# TOP.net
KiCad netlist of a schematic drawn in Altium Designer
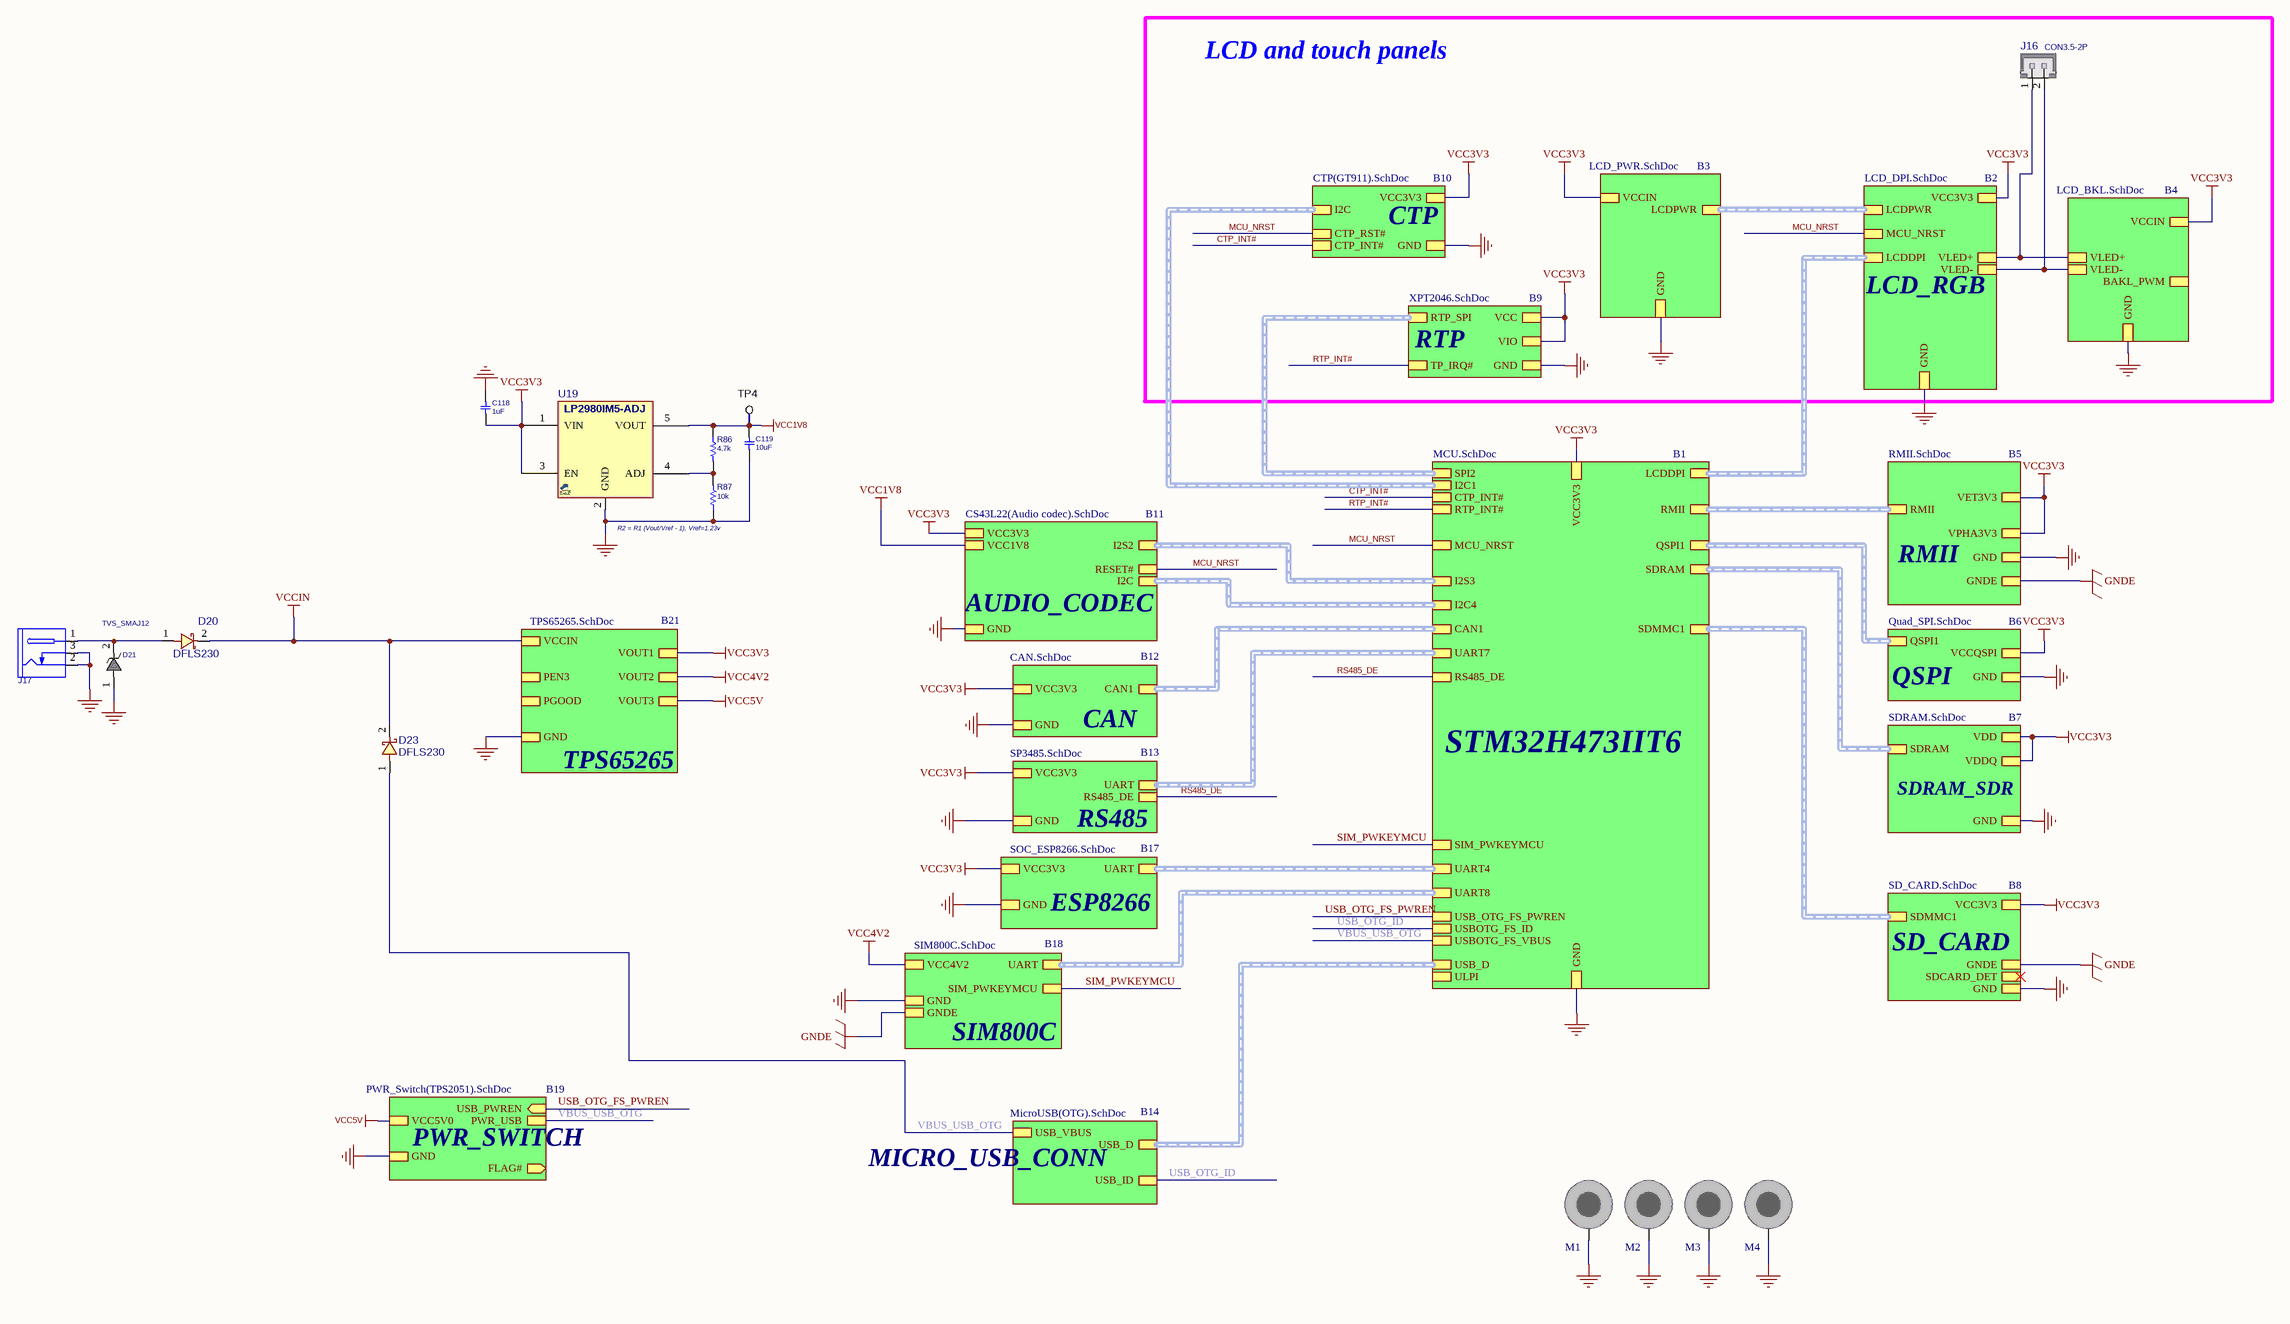
[diagram p0: TOP.SchDoc]

(export (version "E")
  (design (tool "Eeschema 10.0.6"))
  (components
    (comp (ref "C118")
      (value "1uF")
      (footprint "C0805")
      (description "CAP, MLCC")
      (fields (field (name "MANF") "Murata"))
      (libsource (lib "passive_mlcc_smd") (part "CAP_SMD_MLCC_100n50V"))
    )
    (comp (ref "C119")
      (value "10uF")
      (footprint "C0805")
      (description "CAP, MLCC")
      (fields (field (name "MANF") "Murata"))
      (libsource (lib "passive_mlcc_smd") (part "CAP_SMD_MLCC_100n50V"))
    )
    (comp (ref "D20")
      (value "DFLS230")
      (footprint "D_SOD123W")
      (description "DIODE, SCHOTTKY, 30V, 2A")
      (fields (field (name "MANF") "DIODES") (field (name "MANF_P#") "DFLS230LQ-7"))
      (libsource (lib "diode") (part "DIODE_SMD_SCHOTTKY_DFLS230"))
    )
    (comp (ref "D21")
      (value "TVS_SMAJ12")
      (footprint "D_SMA")
      (description "TVS, ESD PROTECT")
      (fields (field (name "MANF_P#") "SMAJ12CA"))
      (libsource (lib "protect_tvs_esd_fuse") (part "TVS_SMAJ6.0A"))
    )
    (comp (ref "D23")
      (value "DFLS230")
      (footprint "D_SOD123W")
      (description "DIODE, SCHOTTKY, 30V, 2A")
      (fields (field (name "MANF") "DIODES") (field (name "MANF_P#") "DFLS230LQ-7"))
      (libsource (lib "diode") (part "DIODE_SMD_SCHOTTKY_DFLS230"))
    )
    (comp (ref "J16")
      (value "CON3.5-2P")
      (footprint "ER_CON3P5_2_SMD")
      (description "CONN, lcd backligh, 3.5mm pitch")
      (fields (field (name "MANF_P#") "ER-CON3.5-2P-SMD"))
      (libsource (lib "conn_wire2board") (part "ER_CON3P5_2_SMD"))
    )
    (comp (ref "J17")
      (value "DC_POWER_JACK")
      (footprint "JAC_PWR1")
      (description "CONN, PWR JACK DC, PLUG DIAM 1.0MM RA THD")
      (fields (field (name "MANF") "CUI STACK") (field (name "MANF_P#") "PJ-031CH, PJ-031C"))
      (libsource (lib "conn_powerJack") (part "CONN_PWR_JACKR1"))
    )
    (comp (ref "M1")
      (value "DNP/MH")
      (footprint "SCMH_M3")
      (description "SCREW mouting, M3, 3.0mm diameter and 6.0mm PanHead")
      (libsource (lib "mech_mountingHole") (part "SCMH_M3"))
    )
    (comp (ref "M2")
      (value "DNP/MH")
      (footprint "SCMH_M3")
      (description "SCREW mouting, M3, 3.0mm diameter and 6.0mm PanHead")
      (libsource (lib "mech_mountingHole") (part "SCMH_M3"))
    )
    (comp (ref "M3")
      (value "DNP/MH")
      (footprint "SCMH_M3")
      (description "SCREW mouting, M3, 3.0mm diameter and 6.0mm PanHead")
      (libsource (lib "mech_mountingHole") (part "SCMH_M3"))
    )
    (comp (ref "M4")
      (value "DNP/MH")
      (footprint "SCMH_M3")
      (description "SCREW mouting, M3, 3.0mm diameter and 6.0mm PanHead")
      (libsource (lib "mech_mountingHole") (part "SCMH_M3"))
    )
    (comp (ref "R86")
      (value "4.7k")
      (footprint "R0805")
      (description "RESISTOR, SMD, 20K, 0402")
      (libsource (lib "chila_passive") (part "RES_SMD"))
    )
    (comp (ref "R87")
      (value "10k")
      (footprint "R0805")
      (description "RESISTOR, SMD, 20K, 0402")
      (libsource (lib "chila_passive") (part "RES_SMD"))
    )
    (comp (ref "TP4")
      (value "TESTPOINT_SMD")
      (footprint "TPSMD_S1")
      (description "TEST POINT")
      (fields (field (name "MANF") "MANF") (field (name "MANF_P#") "MANF_P#"))
      (libsource (lib "test-tp_jumper") (part "TESTPOINT_SMD"))
    )
    (comp (ref "U19")
      (value "LP2980IM5-ADJ")
      (footprint "SOT23_5")
      (description "REG, Linear, LDO0.12V, Adj, 50mA, VIN2.5~16V")
      (fields (field (name "MANF") "Texas Instruments"))
      (libsource (lib "pwr_reg_linear_LDO_highPSRR") (part "VREG_LP2980_SOT23"))
    )
  )
  (nets
    (net (code "29") (name "/VBUS_USB_OTG") (class "Default")
      (node (ref "D23") (pin "1") (pinfunction "1_1") (pintype "passive"))
    )
    (net (code "30") (name "/VLED+") (class "Default")
      (node (ref "J16") (pin "1") (pinfunction "1_1") (pintype "passive"))
    )
    (net (code "31") (name "/VLED-") (class "Default")
      (node (ref "J16") (pin "2") (pinfunction "2_2") (pintype "passive"))
    )
    (net (code "32") (name "GND") (class "Default")
      (node (ref "C118") (pin "1") (pinfunction "1_1") (pintype "passive"))
      (node (ref "C119") (pin "1") (pinfunction "1_1") (pintype "passive"))
      (node (ref "D21") (pin "1") (pinfunction "1_1") (pintype "passive"))
      (node (ref "J17") (pin "2") (pinfunction "SLEEVE_2") (pintype "power_in"))
      (node (ref "J17") (pin "3") (pinfunction "INSERTION_DET_3") (pintype "power_in"))
      (node (ref "M1") (pin "1") (pinfunction "1_1") (pintype "passive"))
      (node (ref "M2") (pin "1") (pinfunction "1_1") (pintype "passive"))
      (node (ref "M3") (pin "1") (pinfunction "1_1") (pintype "passive"))
      (node (ref "M4") (pin "1") (pinfunction "1_1") (pintype "passive"))
      (node (ref "R87") (pin "1") (pinfunction "1_1") (pintype "passive"))
      (node (ref "U19") (pin "2") (pinfunction "GND_2") (pintype "passive"))
    )
    (net (code "34") (name "Net-(J17-TIP)") (class "Default")
      (node (ref "D20") (pin "1") (pinfunction "1_1") (pintype "passive"))
      (node (ref "D21") (pin "2") (pinfunction "2_2") (pintype "passive"))
      (node (ref "J17") (pin "1") (pinfunction "TIP_1") (pintype "power_in"))
    )
    (net (code "35") (name "Net-(U19-ADJ)") (class "Default")
      (node (ref "R86") (pin "2") (pinfunction "2_2") (pintype "passive"))
      (node (ref "R87") (pin "2") (pinfunction "2_2") (pintype "passive"))
      (node (ref "U19") (pin "4") (pinfunction "ADJ_4") (pintype "passive"))
    )
    (net (code "36") (name "VCC1V8") (class "Default")
      (node (ref "C119") (pin "2") (pinfunction "2_2") (pintype "passive"))
      (node (ref "R86") (pin "1") (pinfunction "1_1") (pintype "passive"))
      (node (ref "TP4") (pin "1") (pinfunction "1_1") (pintype "passive"))
      (node (ref "U19") (pin "5") (pinfunction "VOUT_5") (pintype "passive"))
    )
    (net (code "37") (name "VCC3V3") (class "Default")
      (node (ref "C118") (pin "2") (pinfunction "2_2") (pintype "passive"))
      (node (ref "U19") (pin "1") (pinfunction "VIN_1") (pintype "passive"))
      (node (ref "U19") (pin "3") (pinfunction "EN_3") (pintype "passive"))
    )
    (net (code "40") (name "VCCIN") (class "Default")
      (node (ref "D20") (pin "2") (pinfunction "2_2") (pintype "passive"))
      (node (ref "D23") (pin "2") (pinfunction "2_2") (pintype "passive"))
    )
  )
)
